# UnidadDeControl-STM.net
KiCad netlist of a schematic drawn in Altium Designer
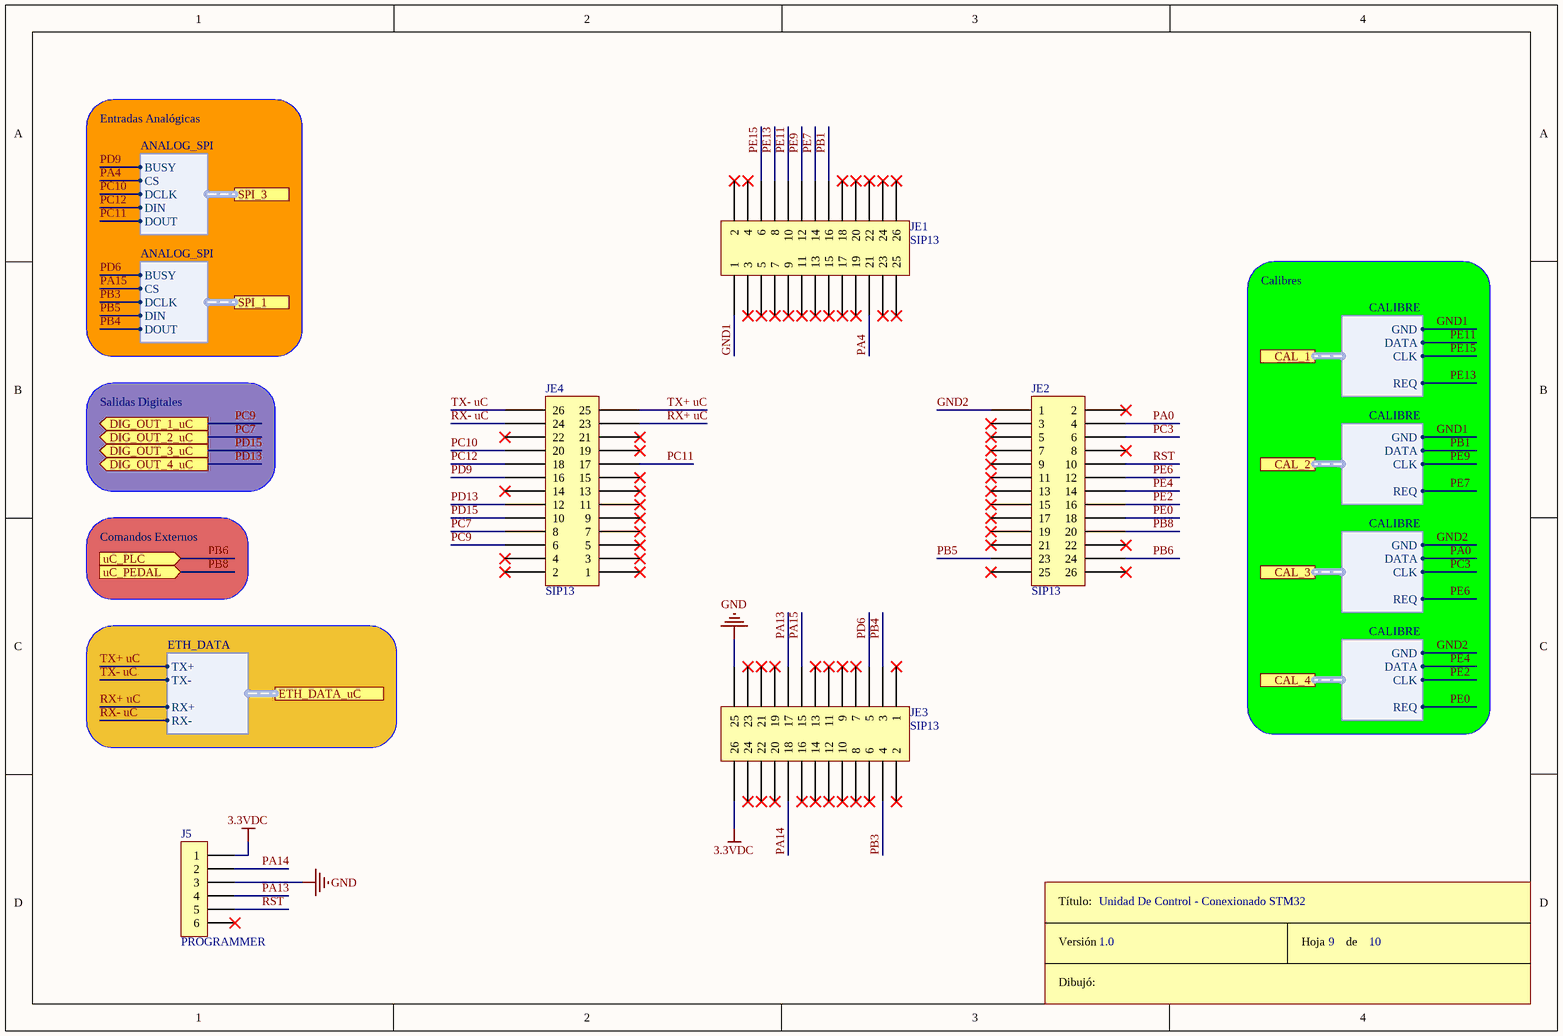
[diagram p0: UnidadDeControl-STM.SchDoc]

(export (version "E")
  (design (tool "Eeschema 10.0.6"))
  (components
    (comp (ref "J5") (value "PROGRAMMER") (footprint "SIP6") (libsource (lib "LIBEBAL") (part "CON6")))
    (comp (ref "JE1") (value "SIP13") (footprint "SIP13*2 - HDR") (libsource (lib "") (part "CON13*2_3")))
    (comp (ref "JE2") (value "SIP13") (footprint "SIP13*2 - HDR") (libsource (lib "") (part "CON13*2_1")))
    (comp (ref "JE3")
      (value "SIP13")
      (footprint "SIP13*2 - HDR")
      (libsource (lib "AditionalComponents") (part "CON13*2"))
    )
    (comp (ref "JE4") (value "SIP13") (footprint "SIP13*2 - HDR") (libsource (lib "") (part "CON13*2_2")))
    (comp (ref "ROT8") (value "Rótulo") (libsource (lib "LIB PIO IX") (part "Rótulo")))
  )
  (nets
    (net (code "4") (name "/GND1") (class "Default")
      (node (ref "JE1") (pin "1") (pinfunction "1_1") (pintype "passive"))
    )
    (net (code "5") (name "/GND2") (class "Default")
      (node (ref "JE2") (pin "1") (pinfunction "1_1") (pintype "passive"))
    )
    (net (code "6") (name "/PA0") (class "Default")
      (node (ref "JE2") (pin "4") (pinfunction "4_4") (pintype "passive"))
    )
    (net (code "7") (name "/PA4") (class "Default")
      (node (ref "JE1") (pin "21") (pinfunction "21_21") (pintype "passive"))
    )
    (net (code "8") (name "/PA13") (class "Default")
      (node (ref "J5") (pin "4") (pinfunction "4_4") (pintype "passive"))
      (node (ref "JE3") (pin "17") (pinfunction "17_17") (pintype "passive"))
    )
    (net (code "9") (name "/PA14") (class "Default")
      (node (ref "J5") (pin "2") (pinfunction "2_2") (pintype "passive"))
      (node (ref "JE3") (pin "18") (pinfunction "18_18") (pintype "passive"))
    )
    (net (code "10") (name "/PA15") (class "Default")
      (node (ref "JE3") (pin "15") (pinfunction "15_15") (pintype "passive"))
    )
    (net (code "11") (name "/PB1") (class "Default")
      (node (ref "JE1") (pin "16") (pinfunction "16_16") (pintype "passive"))
    )
    (net (code "12") (name "/PB3") (class "Default")
      (node (ref "JE3") (pin "4") (pinfunction "4_4") (pintype "passive"))
    )
    (net (code "13") (name "/PB4") (class "Default")
      (node (ref "JE3") (pin "3") (pinfunction "3_3") (pintype "passive"))
    )
    (net (code "14") (name "/PB5") (class "Default")
      (node (ref "JE2") (pin "23") (pinfunction "23_23") (pintype "passive"))
    )
    (net (code "15") (name "/PB6") (class "Default")
      (node (ref "JE2") (pin "24") (pinfunction "24_24") (pintype "passive"))
    )
    (net (code "16") (name "/PB8") (class "Default")
      (node (ref "JE2") (pin "20") (pinfunction "20_20") (pintype "passive"))
    )
    (net (code "17") (name "/PC3") (class "Default")
      (node (ref "JE2") (pin "6") (pinfunction "6_6") (pintype "passive"))
    )
    (net (code "18") (name "/PC7") (class "Default")
      (node (ref "JE4") (pin "8") (pinfunction "8_8") (pintype "passive"))
    )
    (net (code "19") (name "/PC9") (class "Default")
      (node (ref "JE4") (pin "6") (pinfunction "6_6") (pintype "passive"))
    )
    (net (code "20") (name "/PC10") (class "Default")
      (node (ref "JE4") (pin "20") (pinfunction "20_20") (pintype "passive"))
    )
    (net (code "21") (name "/PC11") (class "Default")
      (node (ref "JE4") (pin "17") (pinfunction "17_17") (pintype "passive"))
    )
    (net (code "22") (name "/PC12") (class "Default")
      (node (ref "JE4") (pin "18") (pinfunction "18_18") (pintype "passive"))
    )
    (net (code "23") (name "/PD6") (class "Default")
      (node (ref "JE3") (pin "5") (pinfunction "5_5") (pintype "passive"))
    )
    (net (code "24") (name "/PD9") (class "Default")
      (node (ref "JE4") (pin "16") (pinfunction "16_16") (pintype "passive"))
    )
    (net (code "25") (name "/PD13") (class "Default")
      (node (ref "JE4") (pin "12") (pinfunction "12_12") (pintype "passive"))
    )
    (net (code "26") (name "/PD15") (class "Default")
      (node (ref "JE4") (pin "10") (pinfunction "10_10") (pintype "passive"))
    )
    (net (code "27") (name "/PE0") (class "Default")
      (node (ref "JE2") (pin "18") (pinfunction "18_18") (pintype "passive"))
    )
    (net (code "28") (name "/PE2") (class "Default")
      (node (ref "JE2") (pin "16") (pinfunction "16_16") (pintype "passive"))
    )
    (net (code "29") (name "/PE4") (class "Default")
      (node (ref "JE2") (pin "14") (pinfunction "14_14") (pintype "passive"))
    )
    (net (code "30") (name "/PE6") (class "Default")
      (node (ref "JE2") (pin "12") (pinfunction "12_12") (pintype "passive"))
    )
    (net (code "31") (name "/PE7") (class "Default")
      (node (ref "JE1") (pin "14") (pinfunction "14_14") (pintype "passive"))
    )
    (net (code "32") (name "/PE9") (class "Default")
      (node (ref "JE1") (pin "12") (pinfunction "12_12") (pintype "passive"))
    )
    (net (code "33") (name "/PE11") (class "Default")
      (node (ref "JE1") (pin "10") (pinfunction "10_10") (pintype "passive"))
    )
    (net (code "34") (name "/PE13") (class "Default")
      (node (ref "JE1") (pin "8") (pinfunction "8_8") (pintype "passive"))
    )
    (net (code "35") (name "/PE15") (class "Default")
      (node (ref "JE1") (pin "6") (pinfunction "6_6") (pintype "passive"))
    )
    (net (code "36") (name "/RST") (class "Default")
      (node (ref "J5") (pin "5") (pinfunction "5_5") (pintype "passive"))
      (node (ref "JE2") (pin "10") (pinfunction "10_10") (pintype "passive"))
    )
    (net (code "37") (name "/RX+ uC") (class "Default")
      (node (ref "JE4") (pin "23") (pinfunction "23_23") (pintype "passive"))
    )
    (net (code "38") (name "/RX- uC") (class "Default")
      (node (ref "JE4") (pin "24") (pinfunction "24_24") (pintype "passive"))
    )
    (net (code "39") (name "/TX+ uC") (class "Default")
      (node (ref "JE4") (pin "25") (pinfunction "25_25") (pintype "passive"))
    )
    (net (code "40") (name "/TX- uC") (class "Default")
      (node (ref "JE4") (pin "26") (pinfunction "26_26") (pintype "passive"))
    )
    (net (code "44") (name "3.3VDC") (class "Default")
      (node (ref "J5") (pin "1") (pinfunction "1_1") (pintype "passive"))
      (node (ref "JE3") (pin "26") (pinfunction "26_26") (pintype "passive"))
    )
    (net (code "45") (name "GND") (class "Default")
      (node (ref "J5") (pin "3") (pinfunction "3_3") (pintype "passive"))
      (node (ref "JE3") (pin "25") (pinfunction "25_25") (pintype "passive"))
    )
    (net (code "46") (name "unconnected-(J5-Pad6)") (class "Default")
      (node (ref "J5") (pin "6") (pinfunction "6_6") (pintype "passive+no_connect"))
    )
    (net (code "47") (name "unconnected-(JE1-Pad2)") (class "Default")
      (node (ref "JE1") (pin "2") (pinfunction "2_2") (pintype "passive+no_connect"))
    )
    (net (code "48") (name "unconnected-(JE1-Pad3)") (class "Default")
      (node (ref "JE1") (pin "3") (pinfunction "3_3") (pintype "passive+no_connect"))
    )
    (net (code "49") (name "unconnected-(JE1-Pad4)") (class "Default")
      (node (ref "JE1") (pin "4") (pinfunction "4_4") (pintype "passive+no_connect"))
    )
    (net (code "50") (name "unconnected-(JE1-Pad5)") (class "Default")
      (node (ref "JE1") (pin "5") (pinfunction "5_5") (pintype "passive+no_connect"))
    )
    (net (code "51") (name "unconnected-(JE1-Pad7)") (class "Default")
      (node (ref "JE1") (pin "7") (pinfunction "7_7") (pintype "passive+no_connect"))
    )
    (net (code "52") (name "unconnected-(JE1-Pad9)") (class "Default")
      (node (ref "JE1") (pin "9") (pinfunction "9_9") (pintype "passive+no_connect"))
    )
    (net (code "53") (name "unconnected-(JE1-Pad11)") (class "Default")
      (node (ref "JE1") (pin "11") (pinfunction "11_11") (pintype "passive+no_connect"))
    )
    (net (code "54") (name "unconnected-(JE1-Pad13)") (class "Default")
      (node (ref "JE1") (pin "13") (pinfunction "13_13") (pintype "passive+no_connect"))
    )
    (net (code "55") (name "unconnected-(JE1-Pad15)") (class "Default")
      (node (ref "JE1") (pin "15") (pinfunction "15_15") (pintype "passive+no_connect"))
    )
    (net (code "56") (name "unconnected-(JE1-Pad17)") (class "Default")
      (node (ref "JE1") (pin "17") (pinfunction "17_17") (pintype "passive+no_connect"))
    )
    (net (code "57") (name "unconnected-(JE1-Pad18)") (class "Default")
      (node (ref "JE1") (pin "18") (pinfunction "18_18") (pintype "passive+no_connect"))
    )
    (net (code "58") (name "unconnected-(JE1-Pad19)") (class "Default")
      (node (ref "JE1") (pin "19") (pinfunction "19_19") (pintype "passive+no_connect"))
    )
    (net (code "59") (name "unconnected-(JE1-Pad20)") (class "Default")
      (node (ref "JE1") (pin "20") (pinfunction "20_20") (pintype "passive+no_connect"))
    )
    (net (code "60") (name "unconnected-(JE1-Pad22)") (class "Default")
      (node (ref "JE1") (pin "22") (pinfunction "22_22") (pintype "passive+no_connect"))
    )
    (net (code "61") (name "unconnected-(JE1-Pad23)") (class "Default")
      (node (ref "JE1") (pin "23") (pinfunction "23_23") (pintype "passive+no_connect"))
    )
    (net (code "62") (name "unconnected-(JE1-Pad24)") (class "Default")
      (node (ref "JE1") (pin "24") (pinfunction "24_24") (pintype "passive+no_connect"))
    )
    (net (code "63") (name "unconnected-(JE1-Pad25)") (class "Default")
      (node (ref "JE1") (pin "25") (pinfunction "25_25") (pintype "passive+no_connect"))
    )
    (net (code "64") (name "unconnected-(JE1-Pad26)") (class "Default")
      (node (ref "JE1") (pin "26") (pinfunction "26_26") (pintype "passive+no_connect"))
    )
    (net (code "65") (name "unconnected-(JE2-Pad2)") (class "Default")
      (node (ref "JE2") (pin "2") (pinfunction "2_2") (pintype "passive+no_connect"))
    )
    (net (code "66") (name "unconnected-(JE2-Pad3)") (class "Default")
      (node (ref "JE2") (pin "3") (pinfunction "3_3") (pintype "passive+no_connect"))
    )
    (net (code "67") (name "unconnected-(JE2-Pad5)") (class "Default")
      (node (ref "JE2") (pin "5") (pinfunction "5_5") (pintype "passive+no_connect"))
    )
    (net (code "68") (name "unconnected-(JE2-Pad7)") (class "Default")
      (node (ref "JE2") (pin "7") (pinfunction "7_7") (pintype "passive+no_connect"))
    )
    (net (code "69") (name "unconnected-(JE2-Pad8)") (class "Default")
      (node (ref "JE2") (pin "8") (pinfunction "8_8") (pintype "passive+no_connect"))
    )
    (net (code "70") (name "unconnected-(JE2-Pad9)") (class "Default")
      (node (ref "JE2") (pin "9") (pinfunction "9_9") (pintype "passive+no_connect"))
    )
    (net (code "71") (name "unconnected-(JE2-Pad11)") (class "Default")
      (node (ref "JE2") (pin "11") (pinfunction "11_11") (pintype "passive+no_connect"))
    )
    (net (code "72") (name "unconnected-(JE2-Pad13)") (class "Default")
      (node (ref "JE2") (pin "13") (pinfunction "13_13") (pintype "passive+no_connect"))
    )
    (net (code "73") (name "unconnected-(JE2-Pad15)") (class "Default")
      (node (ref "JE2") (pin "15") (pinfunction "15_15") (pintype "passive+no_connect"))
    )
    (net (code "74") (name "unconnected-(JE2-Pad17)") (class "Default")
      (node (ref "JE2") (pin "17") (pinfunction "17_17") (pintype "passive+no_connect"))
    )
    (net (code "75") (name "unconnected-(JE2-Pad19)") (class "Default")
      (node (ref "JE2") (pin "19") (pinfunction "19_19") (pintype "passive+no_connect"))
    )
    (net (code "76") (name "unconnected-(JE2-Pad21)") (class "Default")
      (node (ref "JE2") (pin "21") (pinfunction "21_21") (pintype "passive+no_connect"))
    )
    (net (code "77") (name "unconnected-(JE2-Pad22)") (class "Default")
      (node (ref "JE2") (pin "22") (pinfunction "22_22") (pintype "passive+no_connect"))
    )
    (net (code "78") (name "unconnected-(JE2-Pad25)") (class "Default")
      (node (ref "JE2") (pin "25") (pinfunction "25_25") (pintype "passive+no_connect"))
    )
    (net (code "79") (name "unconnected-(JE2-Pad26)") (class "Default")
      (node (ref "JE2") (pin "26") (pinfunction "26_26") (pintype "passive+no_connect"))
    )
    (net (code "80") (name "unconnected-(JE3-Pad1)") (class "Default")
      (node (ref "JE3") (pin "1") (pinfunction "1_1") (pintype "passive+no_connect"))
    )
    (net (code "81") (name "unconnected-(JE3-Pad2)") (class "Default")
      (node (ref "JE3") (pin "2") (pinfunction "2_2") (pintype "passive+no_connect"))
    )
    (net (code "82") (name "unconnected-(JE3-Pad6)") (class "Default")
      (node (ref "JE3") (pin "6") (pinfunction "6_6") (pintype "passive+no_connect"))
    )
    (net (code "83") (name "unconnected-(JE3-Pad7)") (class "Default")
      (node (ref "JE3") (pin "7") (pinfunction "7_7") (pintype "passive+no_connect"))
    )
    (net (code "84") (name "unconnected-(JE3-Pad8)") (class "Default")
      (node (ref "JE3") (pin "8") (pinfunction "8_8") (pintype "passive+no_connect"))
    )
    (net (code "85") (name "unconnected-(JE3-Pad9)") (class "Default")
      (node (ref "JE3") (pin "9") (pinfunction "9_9") (pintype "passive+no_connect"))
    )
    (net (code "86") (name "unconnected-(JE3-Pad10)") (class "Default")
      (node (ref "JE3") (pin "10") (pinfunction "10_10") (pintype "passive+no_connect"))
    )
    (net (code "87") (name "unconnected-(JE3-Pad11)") (class "Default")
      (node (ref "JE3") (pin "11") (pinfunction "11_11") (pintype "passive+no_connect"))
    )
    (net (code "88") (name "unconnected-(JE3-Pad12)") (class "Default")
      (node (ref "JE3") (pin "12") (pinfunction "12_12") (pintype "passive+no_connect"))
    )
    (net (code "89") (name "unconnected-(JE3-Pad13)") (class "Default")
      (node (ref "JE3") (pin "13") (pinfunction "13_13") (pintype "passive+no_connect"))
    )
    (net (code "90") (name "unconnected-(JE3-Pad14)") (class "Default")
      (node (ref "JE3") (pin "14") (pinfunction "14_14") (pintype "passive+no_connect"))
    )
    (net (code "91") (name "unconnected-(JE3-Pad16)") (class "Default")
      (node (ref "JE3") (pin "16") (pinfunction "16_16") (pintype "passive+no_connect"))
    )
    (net (code "92") (name "unconnected-(JE3-Pad19)") (class "Default")
      (node (ref "JE3") (pin "19") (pinfunction "19_19") (pintype "passive+no_connect"))
    )
    (net (code "93") (name "unconnected-(JE3-Pad20)") (class "Default")
      (node (ref "JE3") (pin "20") (pinfunction "20_20") (pintype "passive+no_connect"))
    )
    (net (code "94") (name "unconnected-(JE3-Pad21)") (class "Default")
      (node (ref "JE3") (pin "21") (pinfunction "21_21") (pintype "passive+no_connect"))
    )
    (net (code "95") (name "unconnected-(JE3-Pad22)") (class "Default")
      (node (ref "JE3") (pin "22") (pinfunction "22_22") (pintype "passive+no_connect"))
    )
    (net (code "96") (name "unconnected-(JE3-Pad23)") (class "Default")
      (node (ref "JE3") (pin "23") (pinfunction "23_23") (pintype "passive+no_connect"))
    )
    (net (code "97") (name "unconnected-(JE3-Pad24)") (class "Default")
      (node (ref "JE3") (pin "24") (pinfunction "24_24") (pintype "passive+no_connect"))
    )
    (net (code "98") (name "unconnected-(JE4-Pad1)") (class "Default")
      (node (ref "JE4") (pin "1") (pinfunction "1_1") (pintype "passive+no_connect"))
    )
    (net (code "99") (name "unconnected-(JE4-Pad2)") (class "Default")
      (node (ref "JE4") (pin "2") (pinfunction "2_2") (pintype "passive+no_connect"))
    )
    (net (code "100") (name "unconnected-(JE4-Pad3)") (class "Default")
      (node (ref "JE4") (pin "3") (pinfunction "3_3") (pintype "passive+no_connect"))
    )
    (net (code "101") (name "unconnected-(JE4-Pad4)") (class "Default")
      (node (ref "JE4") (pin "4") (pinfunction "4_4") (pintype "passive+no_connect"))
    )
    (net (code "102") (name "unconnected-(JE4-Pad5)") (class "Default")
      (node (ref "JE4") (pin "5") (pinfunction "5_5") (pintype "passive+no_connect"))
    )
    (net (code "103") (name "unconnected-(JE4-Pad7)") (class "Default")
      (node (ref "JE4") (pin "7") (pinfunction "7_7") (pintype "passive+no_connect"))
    )
    (net (code "104") (name "unconnected-(JE4-Pad9)") (class "Default")
      (node (ref "JE4") (pin "9") (pinfunction "9_9") (pintype "passive+no_connect"))
    )
    (net (code "105") (name "unconnected-(JE4-Pad11)") (class "Default")
      (node (ref "JE4") (pin "11") (pinfunction "11_11") (pintype "passive+no_connect"))
    )
    (net (code "106") (name "unconnected-(JE4-Pad13)") (class "Default")
      (node (ref "JE4") (pin "13") (pinfunction "13_13") (pintype "passive+no_connect"))
    )
    (net (code "107") (name "unconnected-(JE4-Pad14)") (class "Default")
      (node (ref "JE4") (pin "14") (pinfunction "14_14") (pintype "passive+no_connect"))
    )
    (net (code "108") (name "unconnected-(JE4-Pad15)") (class "Default")
      (node (ref "JE4") (pin "15") (pinfunction "15_15") (pintype "passive+no_connect"))
    )
    (net (code "109") (name "unconnected-(JE4-Pad19)") (class "Default")
      (node (ref "JE4") (pin "19") (pinfunction "19_19") (pintype "passive+no_connect"))
    )
    (net (code "110") (name "unconnected-(JE4-Pad21)") (class "Default")
      (node (ref "JE4") (pin "21") (pinfunction "21_21") (pintype "passive+no_connect"))
    )
    (net (code "111") (name "unconnected-(JE4-Pad22)") (class "Default")
      (node (ref "JE4") (pin "22") (pinfunction "22_22") (pintype "passive+no_connect"))
    )
  )
)
